# P5a_Filter1A.net
KiCad netlist of a schematic drawn in Altium Designer
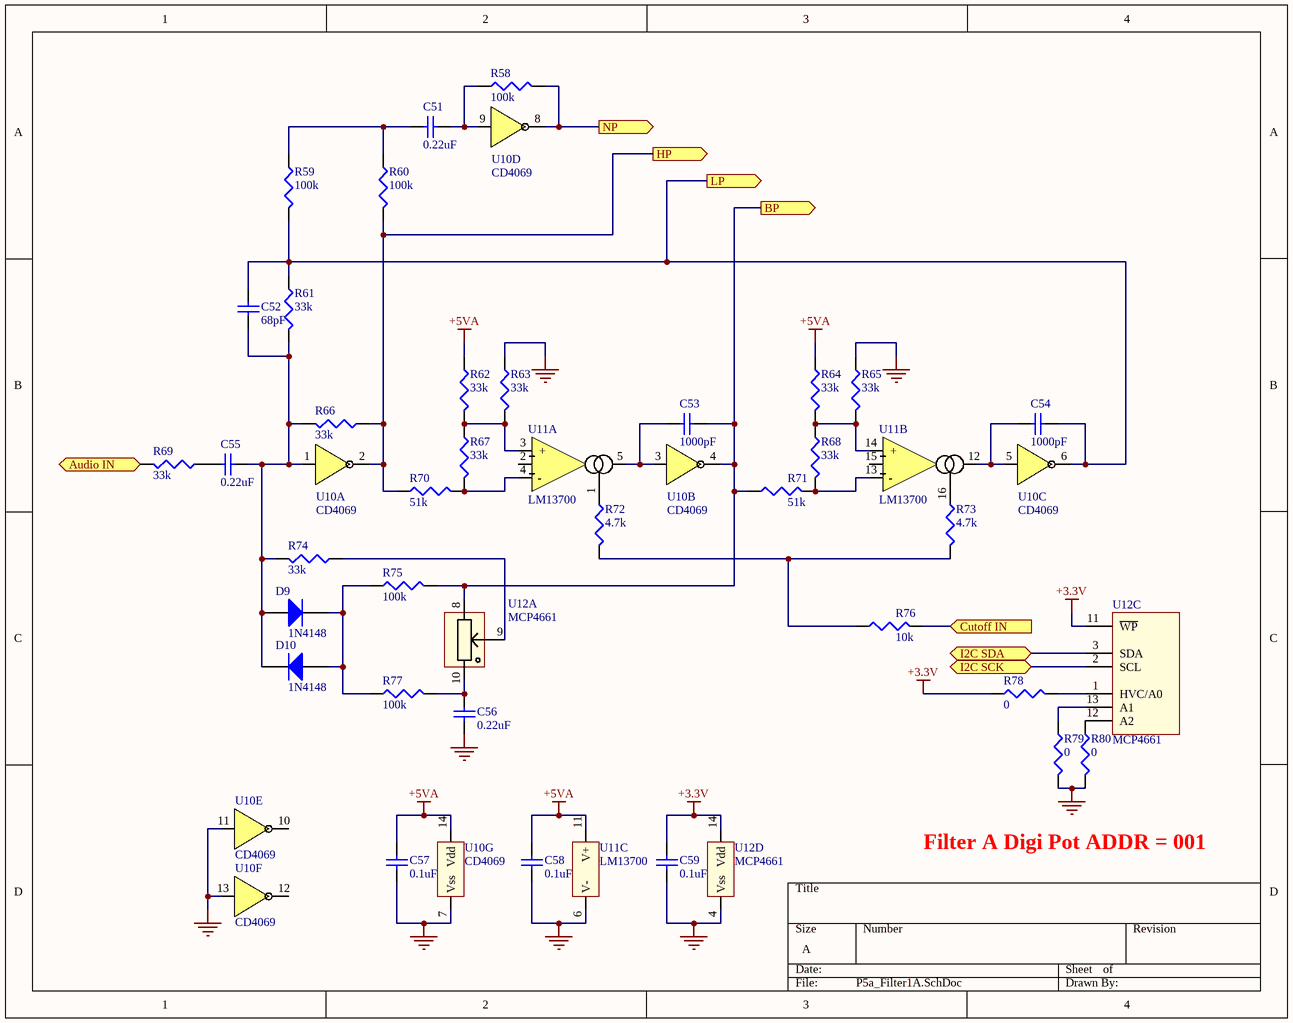
[diagram p0: P5a_Filter1A.SchDoc]

(export (version "E")
  (design (tool "Eeschema 10.0.6"))
  (components
    (comp (ref "C51")
      (value "0.22uF")
      (footprint "CAP 0603 (1608 metric)")
      (description "Capacitor (Semiconductor SIM Model)")
      (libsource (lib "Miscellaneous Devices") (part "Cap Semi"))
    )
    (comp (ref "C52")
      (value "68pF")
      (footprint "CAP 0603 (1608 metric)")
      (description "Capacitor (Semiconductor SIM Model)")
      (libsource (lib "Miscellaneous Devices") (part "Cap Semi"))
    )
    (comp (ref "C53")
      (value "1000pF")
      (footprint "CAP 0603 (1608 metric)")
      (description "Capacitor (Semiconductor SIM Model)")
      (libsource (lib "Miscellaneous Devices") (part "Cap Semi"))
    )
    (comp (ref "C54")
      (value "1000pF")
      (footprint "CAP 0603 (1608 metric)")
      (description "Capacitor (Semiconductor SIM Model)")
      (libsource (lib "Miscellaneous Devices") (part "Cap Semi"))
    )
    (comp (ref "C55")
      (value "0.22uF")
      (footprint "CAP 0603 (1608 metric)")
      (description "Capacitor (Semiconductor SIM Model)")
      (libsource (lib "Miscellaneous Devices") (part "Cap Semi"))
    )
    (comp (ref "C56")
      (value "0.22uF")
      (footprint "CAP 0603 (1608 metric)")
      (description "Capacitor (Semiconductor SIM Model)")
      (libsource (lib "Miscellaneous Devices") (part "Cap Semi"))
    )
    (comp (ref "C57")
      (value "0.1uF")
      (footprint "CAP 0603 (1608 metric)")
      (description "Capacitor (Semiconductor SIM Model)")
      (libsource (lib "Miscellaneous Devices") (part "Cap Semi"))
    )
    (comp (ref "C58")
      (value "0.1uF")
      (footprint "CAP 0603 (1608 metric)")
      (description "Capacitor (Semiconductor SIM Model)")
      (libsource (lib "Miscellaneous Devices") (part "Cap Semi"))
    )
    (comp (ref "C59")
      (value "0.1uF")
      (footprint "CAP 0603 (1608 metric)")
      (description "Capacitor (Semiconductor SIM Model)")
      (libsource (lib "Miscellaneous Devices") (part "Cap Semi"))
    )
    (comp (ref "D9")
      (value "1N4148")
      (description "High Conductance Fast Diode")
      (libsource (lib "Miscellaneous Devices") (part "Diode 1N4148"))
    )
    (comp (ref "D10")
      (value "1N4148")
      (description "High Conductance Fast Diode")
      (libsource (lib "Miscellaneous Devices") (part "Diode 1N4148"))
    )
    (comp (ref "R58")
      (value "100k")
      (footprint "RES 0603 (1608 metric)")
      (description "Resistor")
      (libsource (lib "Miscellaneous Devices") (part "Res3"))
    )
    (comp (ref "R59")
      (value "100k")
      (footprint "RES 0603 (1608 metric)")
      (description "Resistor")
      (libsource (lib "Miscellaneous Devices") (part "Res3"))
    )
    (comp (ref "R60")
      (value "100k")
      (footprint "RES 0603 (1608 metric)")
      (description "Resistor")
      (libsource (lib "Miscellaneous Devices") (part "Res3"))
    )
    (comp (ref "R61")
      (value "33k")
      (footprint "RES 0603 (1608 metric)")
      (description "Resistor")
      (libsource (lib "Miscellaneous Devices") (part "Res3"))
    )
    (comp (ref "R62")
      (value "33k")
      (footprint "RES 0603 (1608 metric)")
      (description "Resistor")
      (libsource (lib "Miscellaneous Devices") (part "Res3"))
    )
    (comp (ref "R63")
      (value "33k")
      (footprint "RES 0603 (1608 metric)")
      (description "Resistor")
      (libsource (lib "Miscellaneous Devices") (part "Res3"))
    )
    (comp (ref "R64")
      (value "33k")
      (footprint "RES 0603 (1608 metric)")
      (description "Resistor")
      (libsource (lib "Miscellaneous Devices") (part "Res3"))
    )
    (comp (ref "R65")
      (value "33k")
      (footprint "RES 0603 (1608 metric)")
      (description "Resistor")
      (libsource (lib "Miscellaneous Devices") (part "Res3"))
    )
    (comp (ref "R66")
      (value "33k")
      (footprint "RES 0603 (1608 metric)")
      (description "Resistor")
      (libsource (lib "Miscellaneous Devices") (part "Res3"))
    )
    (comp (ref "R67")
      (value "33k")
      (footprint "RES 0603 (1608 metric)")
      (description "Resistor")
      (libsource (lib "Miscellaneous Devices") (part "Res3"))
    )
    (comp (ref "R68")
      (value "33k")
      (footprint "RES 0603 (1608 metric)")
      (description "Resistor")
      (libsource (lib "Miscellaneous Devices") (part "Res3"))
    )
    (comp (ref "R69")
      (value "33k")
      (footprint "RES 0603 (1608 metric)")
      (description "Resistor")
      (libsource (lib "Miscellaneous Devices") (part "Res3"))
    )
    (comp (ref "R70")
      (value "51k")
      (footprint "RES 0603 (1608 metric)")
      (description "Resistor")
      (libsource (lib "Miscellaneous Devices") (part "Res3"))
    )
    (comp (ref "R71")
      (value "51k")
      (footprint "RES 0603 (1608 metric)")
      (description "Resistor")
      (libsource (lib "Miscellaneous Devices") (part "Res3"))
    )
    (comp (ref "R72")
      (value "4.7k")
      (footprint "RES 0603 (1608 metric)")
      (description "Resistor")
      (libsource (lib "Miscellaneous Devices") (part "Res3"))
    )
    (comp (ref "R73")
      (value "4.7k")
      (footprint "RES 0603 (1608 metric)")
      (description "Resistor")
      (libsource (lib "Miscellaneous Devices") (part "Res3"))
    )
    (comp (ref "R74")
      (value "33k")
      (footprint "RES 0603 (1608 metric)")
      (description "Resistor")
      (libsource (lib "Miscellaneous Devices") (part "Res3"))
    )
    (comp (ref "R75")
      (value "100k")
      (footprint "RES 0603 (1608 metric)")
      (description "Resistor")
      (libsource (lib "Miscellaneous Devices") (part "Res3"))
    )
    (comp (ref "R76")
      (value "10k")
      (footprint "RES 0603 (1608 metric)")
      (description "Resistor")
      (libsource (lib "Miscellaneous Devices") (part "Res3"))
    )
    (comp (ref "R77")
      (value "100k")
      (footprint "RES 0603 (1608 metric)")
      (description "Resistor")
      (libsource (lib "Miscellaneous Devices") (part "Res3"))
    )
    (comp (ref "R78")
      (value "0")
      (footprint "RES 0603 (1608 metric)")
      (description "Resistor")
      (libsource (lib "Miscellaneous Devices") (part "Res3"))
    )
    (comp (ref "R79")
      (value "0")
      (footprint "RES 0603 (1608 metric)")
      (description "Resistor")
      (libsource (lib "Miscellaneous Devices") (part "Res3"))
    )
    (comp (ref "R80")
      (value "0")
      (footprint "RES 0603 (1608 metric)")
      (description "Resistor")
      (libsource (lib "Miscellaneous Devices") (part "Res3"))
    )
    (comp (ref "U10")
      (value "CD4069")
      (description "Hex Inverter")
      (libsource (lib "FilterPoC") (part "CD4069"))
    )
    (comp (ref "U11")
      (value "LM13700")
      (description "Dual Transconductance OpAmp")
      (libsource (lib "FilterPoC") (part "LM13700M"))
    )
    (comp (ref "U12")
      (value "MCP4661")
      (description "Dual DigiPot non volatile I2C")
      (libsource (lib "FilterPoC") (part "MCP4661"))
    )
  )
  (nets
    (net (code "1") (name "+3.3V") (class "Default")
      (node (ref "C59") (pin "1") (pinfunction "1_1") (pintype "passive"))
      (node (ref "R78") (pin "1") (pinfunction "1_1") (pintype "passive"))
      (node (ref "U12") (pin "11") (pinfunction "~{WP}_11") (pintype "passive"))
      (node (ref "U12") (pin "14") (pinfunction "Vdd_14") (pintype "power_in"))
    )
    (net (code "2") (name "+5VA") (class "Default")
      (node (ref "C57") (pin "1") (pinfunction "1_1") (pintype "passive"))
      (node (ref "C58") (pin "1") (pinfunction "1_1") (pintype "passive"))
      (node (ref "R62") (pin "1") (pinfunction "1_1") (pintype "passive"))
      (node (ref "R64") (pin "1") (pinfunction "1_1") (pintype "passive"))
      (node (ref "U10") (pin "14") (pinfunction "Vdd_14") (pintype "power_in"))
      (node (ref "U11") (pin "11") (pinfunction "V+_11") (pintype "power_in"))
    )
    (net (code "3") (name "/Audio IN") (class "Default")
      (node (ref "R69") (pin "2") (pinfunction "2_2") (pintype "passive"))
    )
    (net (code "4") (name "/BP") (class "Default")
      (node (ref "C53") (pin "2") (pinfunction "2_2") (pintype "passive"))
      (node (ref "R71") (pin "1") (pinfunction "1_1") (pintype "passive"))
      (node (ref "R75") (pin "2") (pinfunction "2_2") (pintype "passive"))
      (node (ref "U10") (pin "4") (pinfunction "~{B}_4") (pintype "passive"))
      (node (ref "U12") (pin "8") (pinfunction "P0A_8") (pintype "passive"))
    )
    (net (code "5") (name "/Cutoff IN") (class "Default")
      (node (ref "R76") (pin "2") (pinfunction "2_2") (pintype "passive"))
    )
    (net (code "6") (name "/HP") (class "Default")
      (node (ref "R60") (pin "2") (pinfunction "2_2") (pintype "passive"))
      (node (ref "R66") (pin "1") (pinfunction "1_1") (pintype "passive"))
      (node (ref "R70") (pin "1") (pinfunction "1_1") (pintype "passive"))
      (node (ref "U10") (pin "2") (pinfunction "~{A}_2") (pintype "passive"))
    )
    (net (code "7") (name "/I2C SCK") (class "Default")
      (node (ref "U12") (pin "2") (pinfunction "SCL_2") (pintype "passive"))
    )
    (net (code "8") (name "/I2C SDA") (class "Default")
      (node (ref "U12") (pin "3") (pinfunction "SDA_3") (pintype "passive"))
    )
    (net (code "9") (name "/LP") (class "Default")
      (node (ref "C52") (pin "2") (pinfunction "2_2") (pintype "passive"))
      (node (ref "C54") (pin "2") (pinfunction "2_2") (pintype "passive"))
      (node (ref "R59") (pin "2") (pinfunction "2_2") (pintype "passive"))
      (node (ref "R61") (pin "1") (pinfunction "1_1") (pintype "passive"))
      (node (ref "U10") (pin "6") (pinfunction "~{C}_6") (pintype "passive"))
    )
    (net (code "10") (name "/NP") (class "Default")
      (node (ref "R58") (pin "2") (pinfunction "2_2") (pintype "passive"))
      (node (ref "U10") (pin "8") (pinfunction "~{D}_8") (pintype "passive"))
    )
    (net (code "11") (name "GND") (class "Default")
      (node (ref "C56") (pin "2") (pinfunction "2_2") (pintype "passive"))
      (node (ref "C57") (pin "2") (pinfunction "2_2") (pintype "passive"))
      (node (ref "C58") (pin "2") (pinfunction "2_2") (pintype "passive"))
      (node (ref "C59") (pin "2") (pinfunction "2_2") (pintype "passive"))
      (node (ref "R63") (pin "1") (pinfunction "1_1") (pintype "passive"))
      (node (ref "R65") (pin "1") (pinfunction "1_1") (pintype "passive"))
      (node (ref "R79") (pin "2") (pinfunction "2_2") (pintype "passive"))
      (node (ref "R80") (pin "2") (pinfunction "2_2") (pintype "passive"))
      (node (ref "U10") (pin "11") (pinfunction "E_11") (pintype "passive"))
      (node (ref "U10") (pin "13") (pinfunction "F_13") (pintype "passive"))
      (node (ref "U10") (pin "7") (pinfunction "Vss_7") (pintype "power_in"))
      (node (ref "U11") (pin "6") (pinfunction "V-_6") (pintype "power_in"))
      (node (ref "U12") (pin "4") (pinfunction "Vss_4") (pintype "power_in"))
    )
    (net (code "12") (name "Net-(C51-Pad1)") (class "Default")
      (node (ref "C51") (pin "1") (pinfunction "1_1") (pintype "passive"))
      (node (ref "R59") (pin "1") (pinfunction "1_1") (pintype "passive"))
      (node (ref "R60") (pin "1") (pinfunction "1_1") (pintype "passive"))
    )
    (net (code "13") (name "Net-(C55-Pad1)") (class "Default")
      (node (ref "C55") (pin "1") (pinfunction "1_1") (pintype "passive"))
      (node (ref "R69") (pin "1") (pinfunction "1_1") (pintype "passive"))
    )
    (net (code "14") (name "Net-(D10-A)") (class "Default")
      (node (ref "D10") (pin "1") (pinfunction "A_1") (pintype "passive"))
      (node (ref "D9") (pin "2") (pinfunction "K_2") (pintype "passive"))
      (node (ref "R75") (pin "1") (pinfunction "1_1") (pintype "passive"))
      (node (ref "R77") (pin "1") (pinfunction "1_1") (pintype "passive"))
    )
    (net (code "15") (name "Net-(D10-K)") (class "Default")
      (node (ref "C52") (pin "1") (pinfunction "1_1") (pintype "passive"))
      (node (ref "C55") (pin "2") (pinfunction "2_2") (pintype "passive"))
      (node (ref "D10") (pin "2") (pinfunction "K_2") (pintype "passive"))
      (node (ref "D9") (pin "1") (pinfunction "A_1") (pintype "passive"))
      (node (ref "R61") (pin "2") (pinfunction "2_2") (pintype "passive"))
      (node (ref "R66") (pin "2") (pinfunction "2_2") (pintype "passive"))
      (node (ref "R74") (pin "2") (pinfunction "2_2") (pintype "passive"))
      (node (ref "U10") (pin "1") (pinfunction "A_1") (pintype "passive"))
    )
    (net (code "16") (name "Net-(R72-Pad2)") (class "Default")
      (node (ref "R72") (pin "2") (pinfunction "2_2") (pintype "passive"))
      (node (ref "R73") (pin "2") (pinfunction "2_2") (pintype "passive"))
      (node (ref "R76") (pin "1") (pinfunction "1_1") (pintype "passive"))
    )
    (net (code "17") (name "Net-(U10B-B)") (class "Default")
      (node (ref "C53") (pin "1") (pinfunction "1_1") (pintype "passive"))
      (node (ref "U10") (pin "3") (pinfunction "B_3") (pintype "passive"))
      (node (ref "U11") (pin "5") (pinfunction "OUT_5") (pintype "passive"))
    )
    (net (code "18") (name "Net-(U10C-C)") (class "Default")
      (node (ref "C54") (pin "1") (pinfunction "1_1") (pintype "passive"))
      (node (ref "U10") (pin "5") (pinfunction "C_5") (pintype "passive"))
      (node (ref "U11") (pin "12") (pinfunction "OUT_12") (pintype "passive"))
    )
    (net (code "19") (name "Net-(U10D-D)") (class "Default")
      (node (ref "C51") (pin "2") (pinfunction "2_2") (pintype "passive"))
      (node (ref "R58") (pin "1") (pinfunction "1_1") (pintype "passive"))
      (node (ref "U10") (pin "9") (pinfunction "D_9") (pintype "passive"))
    )
    (net (code "20") (name "Net-(U11A-+)") (class "Default")
      (node (ref "R62") (pin "2") (pinfunction "2_2") (pintype "passive"))
      (node (ref "R63") (pin "2") (pinfunction "2_2") (pintype "passive"))
      (node (ref "R67") (pin "1") (pinfunction "1_1") (pintype "passive"))
      (node (ref "U11") (pin "3") (pinfunction "+_3") (pintype "passive"))
    )
    (net (code "21") (name "Net-(U11A--)") (class "Default")
      (node (ref "R67") (pin "2") (pinfunction "2_2") (pintype "passive"))
      (node (ref "R70") (pin "2") (pinfunction "2_2") (pintype "passive"))
      (node (ref "U11") (pin "4") (pinfunction "-_4") (pintype "passive"))
    )
    (net (code "22") (name "Net-(U11A-BIAS)") (class "Default")
      (node (ref "R72") (pin "1") (pinfunction "1_1") (pintype "passive"))
      (node (ref "U11") (pin "1") (pinfunction "BIAS_1") (pintype "passive"))
    )
    (net (code "23") (name "Net-(U11B-+)") (class "Default")
      (node (ref "R64") (pin "2") (pinfunction "2_2") (pintype "passive"))
      (node (ref "R65") (pin "2") (pinfunction "2_2") (pintype "passive"))
      (node (ref "R68") (pin "1") (pinfunction "1_1") (pintype "passive"))
      (node (ref "U11") (pin "14") (pinfunction "+_14") (pintype "passive"))
    )
    (net (code "24") (name "Net-(U11B--)") (class "Default")
      (node (ref "R68") (pin "2") (pinfunction "2_2") (pintype "passive"))
      (node (ref "R71") (pin "2") (pinfunction "2_2") (pintype "passive"))
      (node (ref "U11") (pin "13") (pinfunction "-_13") (pintype "passive"))
    )
    (net (code "25") (name "Net-(U11B-BIAS)") (class "Default")
      (node (ref "R73") (pin "1") (pinfunction "1_1") (pintype "passive"))
      (node (ref "U11") (pin "16") (pinfunction "BIAS_16") (pintype "passive"))
    )
    (net (code "26") (name "Net-(U12A-P0B)") (class "Default")
      (node (ref "C56") (pin "1") (pinfunction "1_1") (pintype "passive"))
      (node (ref "R77") (pin "2") (pinfunction "2_2") (pintype "passive"))
      (node (ref "U12") (pin "10") (pinfunction "P0B_10") (pintype "passive"))
    )
    (net (code "27") (name "Net-(U12A-P0W)") (class "Default")
      (node (ref "R74") (pin "1") (pinfunction "1_1") (pintype "passive"))
      (node (ref "U12") (pin "9") (pinfunction "P0W_9") (pintype "passive"))
    )
    (net (code "28") (name "Net-(U12C-A1)") (class "Default")
      (node (ref "R79") (pin "1") (pinfunction "1_1") (pintype "passive"))
      (node (ref "U12") (pin "13") (pinfunction "A1_13") (pintype "power_in"))
    )
    (net (code "29") (name "Net-(U12C-A2)") (class "Default")
      (node (ref "R80") (pin "1") (pinfunction "1_1") (pintype "passive"))
      (node (ref "U12") (pin "12") (pinfunction "A2_12") (pintype "power_in"))
    )
    (net (code "30") (name "Net-(U12C-HVC{slash}A0)") (class "Default")
      (node (ref "R78") (pin "2") (pinfunction "2_2") (pintype "passive"))
      (node (ref "U12") (pin "1") (pinfunction "HVC/A0_1") (pintype "power_in"))
    )
    (net (code "31") (name "unconnected-(U10E-~{E}-Pad10)") (class "Default")
      (node (ref "U10") (pin "10") (pinfunction "~{E}_10") (pintype "passive"))
    )
    (net (code "32") (name "unconnected-(U10F-~{F}-Pad12)") (class "Default")
      (node (ref "U10") (pin "12") (pinfunction "~{F}_12") (pintype "passive"))
    )
    (net (code "33") (name "unconnected-(U11A-Diode_BIAS-Pad2)") (class "Default")
      (node (ref "U11") (pin "2") (pinfunction "Diode_BIAS_2") (pintype "passive"))
    )
    (net (code "34") (name "unconnected-(U11B-Diode_BIAS-Pad15)") (class "Default")
      (node (ref "U11") (pin "15") (pinfunction "Diode_BIAS_15") (pintype "passive"))
    )
  )
)
